# PCB-GONIO-V1_1.net
KiCad netlist of a schematic drawn in EAGLE
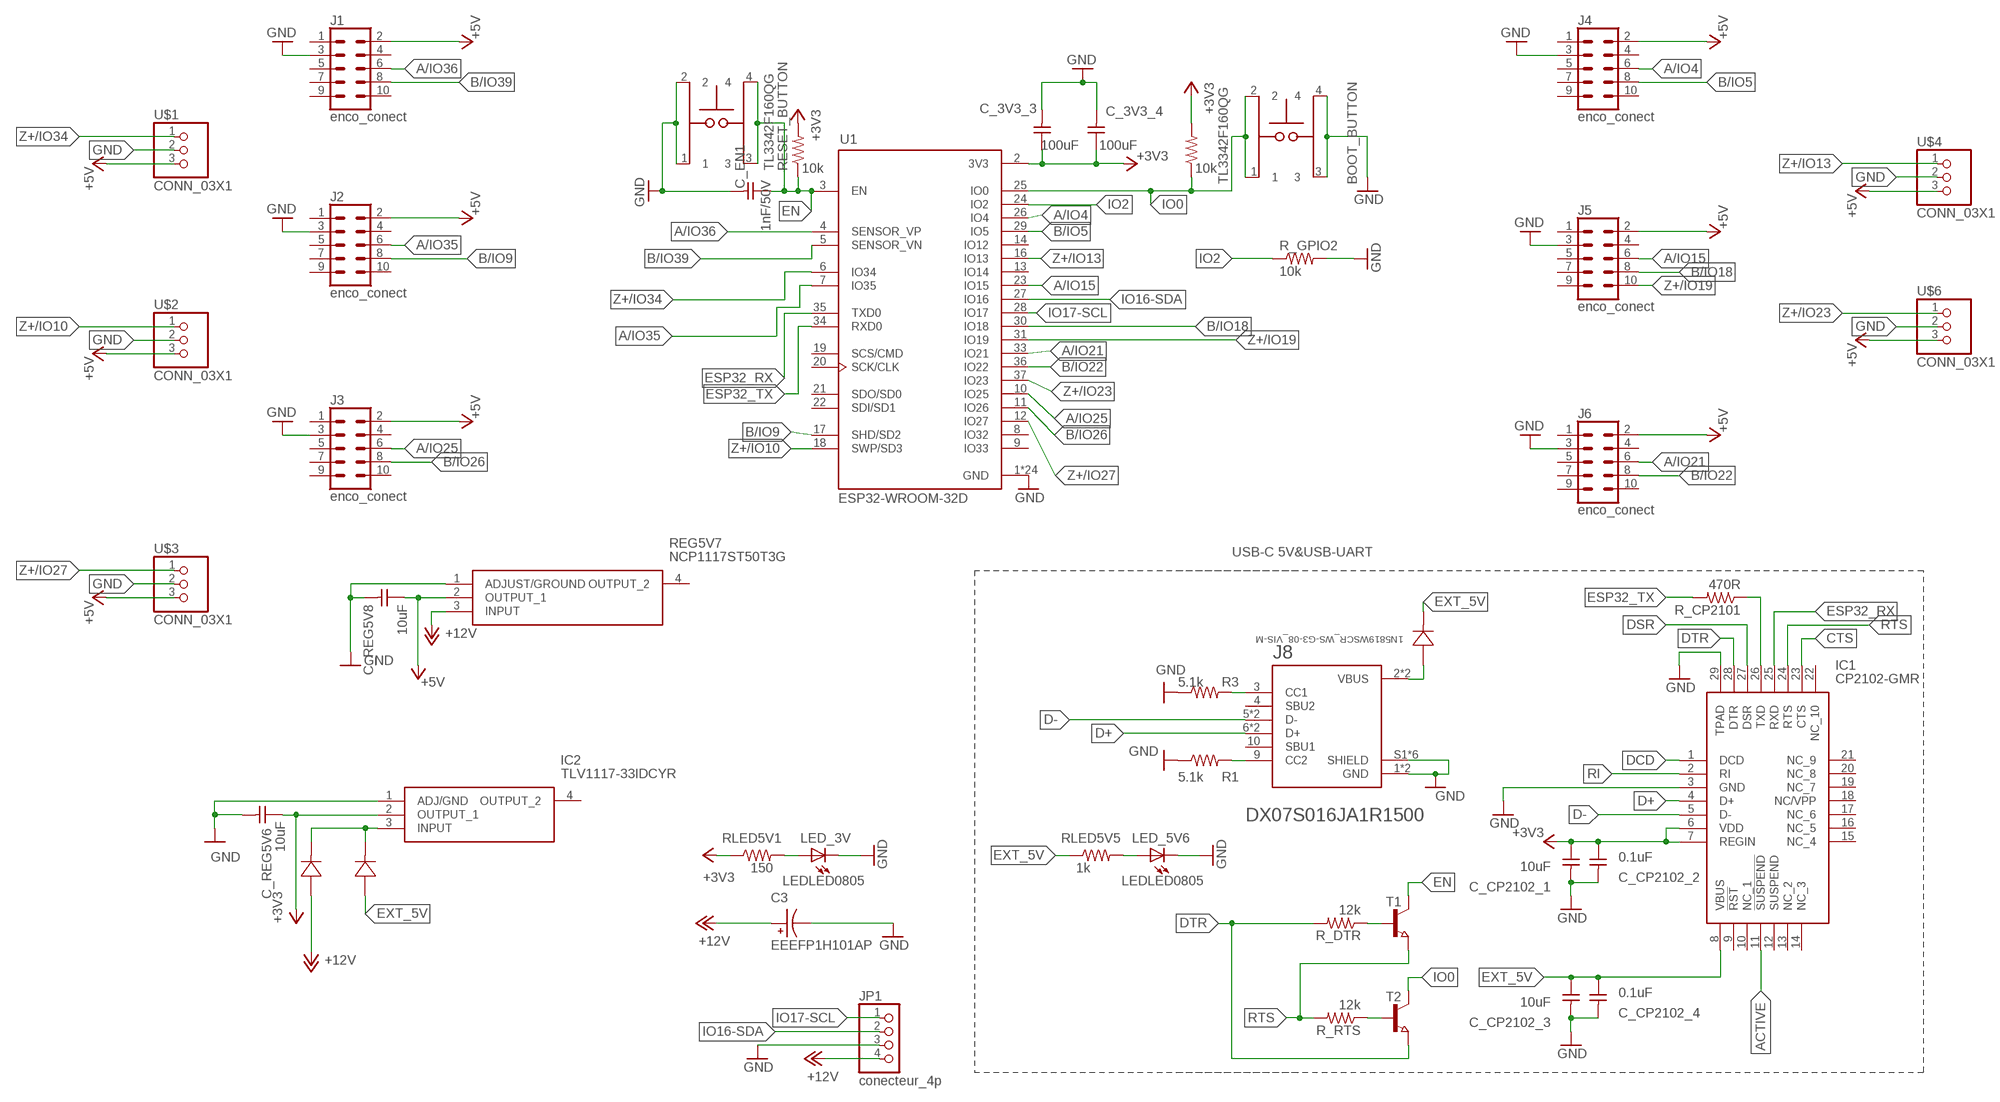
[diagram p0: schematic, sheet 1]

(export (version "E")
  (design (tool "Eeschema 10.0.6"))
  (components
    (comp (ref "BOOT_BUTTON")
      (value "TL3342F160QG")
      (footprint "eagle-import:SW_TL3342F160QG")
      (fields (field (name "MF") "E-Switch"))
      (libsource (lib "eagle-import") (part "TL3342F160QG"))
    )
    (comp (ref "C3")
      (value "EEEFP1H101AP")
      (footprint "eagle-import:CAP_EEEFP1H101AP")
      (fields (field (name "DIGIKEY_PART_NUMBER") "P19726TR-ND") (field (name "MF") "Panasonic"))
      (libsource (lib "eagle-import") (part "EEEFP1H101AP"))
    )
    (comp (ref "CR1")
      (value "1N5819WSCR_WS-G3-08_VIS-M")
      (footprint "eagle-import:CR_WS-G3-08_VIS-M")
      (fields
        (field (name "MANUFACTURER_PART_NUMBER") "1N4148WS-G3-08")
        (field (name "COPYRIGHT") "Copyright (C) 2022 Ultra Librarian. All rights reserved.")
      )
      (libsource (lib "eagle-import") (part "1N5819WSCR_WS-G3-08_VIS-M"))
    )
    (comp (ref "CR2")
      (value "1N5819WSCR_WS-G3-08_VIS-M")
      (footprint "eagle-import:CR_WS-G3-08_VIS-M")
      (fields
        (field (name "MANUFACTURER_PART_NUMBER") "1N4148WS-G3-08")
        (field (name "COPYRIGHT") "Copyright (C) 2022 Ultra Librarian. All rights reserved.")
      )
      (libsource (lib "eagle-import") (part "1N5819WSCR_WS-G3-08_VIS-M"))
    )
    (comp (ref "CR3")
      (value "1N5819WSCR_WS-G3-08_VIS-M")
      (footprint "eagle-import:CR_WS-G3-08_VIS-M")
      (fields
        (field (name "MANUFACTURER_PART_NUMBER") "1N4148WS-G3-08")
        (field (name "COPYRIGHT") "Copyright (C) 2022 Ultra Librarian. All rights reserved.")
      )
      (libsource (lib "eagle-import") (part "1N5819WSCR_WS-G3-08_VIS-M"))
    )
    (comp (ref "C_3V3_3")
      (value "100uF")
      (footprint "eagle-import:C1206FAB")
      (libsource (lib "eagle-import") (part "CAP_UNPOLARIZEDFAB"))
    )
    (comp (ref "C_3V3_4")
      (value "100uF")
      (footprint "eagle-import:C1206FAB")
      (libsource (lib "eagle-import") (part "CAP_UNPOLARIZEDFAB"))
    )
    (comp (ref "C_CP2102_1")
      (value "10uF")
      (footprint "eagle-import:C1206FAB")
      (libsource (lib "eagle-import") (part "CAP_UNPOLARIZEDFAB"))
    )
    (comp (ref "C_CP2102_2")
      (value "0.1uF")
      (footprint "eagle-import:C1206FAB")
      (libsource (lib "eagle-import") (part "CAP_UNPOLARIZEDFAB"))
    )
    (comp (ref "C_CP2102_3")
      (value "10uF")
      (footprint "eagle-import:C1206FAB")
      (libsource (lib "eagle-import") (part "CAP_UNPOLARIZEDFAB"))
    )
    (comp (ref "C_CP2102_4")
      (value "0.1uF")
      (footprint "eagle-import:C1206FAB")
      (libsource (lib "eagle-import") (part "CAP_UNPOLARIZEDFAB"))
    )
    (comp (ref "C_EN1")
      (value "1nF/50V")
      (footprint "eagle-import:C1206FAB")
      (libsource (lib "eagle-import") (part "CAP_UNPOLARIZEDFAB"))
    )
    (comp (ref "C_REG5V6")
      (value "10uF")
      (footprint "eagle-import:C1206FAB")
      (libsource (lib "eagle-import") (part "CAP_UNPOLARIZEDFAB"))
    )
    (comp (ref "C_REG5V8")
      (value "10uF")
      (footprint "eagle-import:C1206FAB")
      (libsource (lib "eagle-import") (part "CAP_UNPOLARIZEDFAB"))
    )
    (comp (ref "IC1")
      (value "CP2102-GMR")
      (footprint "eagle-import:QFN50P500X500X100-29N")
      (fields (field (name "MOUSER_PART_NUMBER") "634-CP2102-GMR"))
      (libsource (lib "eagle-import") (part "CP2102-GMR"))
    )
    (comp (ref "IC2")
      (value "TLV1117-33IDCYR")
      (footprint "eagle-import:SOT230P700X180-4N")
      (fields (field (name "MOUSER_PART_NUMBER") "595-TLV1117-33IDCYR"))
      (libsource (lib "eagle-import") (part "TLV1117-33IDCYR"))
    )
    (comp (ref "J1")
      (value "enco_conect")
      (footprint "eagle-import:2X5-SHROUDED")
      (libsource (lib "eagle-import") (part "CONN_05X2SHD"))
    )
    (comp (ref "J2")
      (value "enco_conect")
      (footprint "eagle-import:2X5-SHROUDED")
      (libsource (lib "eagle-import") (part "CONN_05X2SHD"))
    )
    (comp (ref "J3")
      (value "enco_conect")
      (footprint "eagle-import:2X5-SHROUDED")
      (libsource (lib "eagle-import") (part "CONN_05X2SHD"))
    )
    (comp (ref "J4")
      (value "enco_conect")
      (footprint "eagle-import:2X5-SHROUDED")
      (libsource (lib "eagle-import") (part "CONN_05X2SHD"))
    )
    (comp (ref "J5")
      (value "enco_conect")
      (footprint "eagle-import:2X5-SHROUDED")
      (libsource (lib "eagle-import") (part "CONN_05X2SHD"))
    )
    (comp (ref "J6")
      (value "enco_conect")
      (footprint "eagle-import:2X5-SHROUDED")
      (libsource (lib "eagle-import") (part "CONN_05X2SHD"))
    )
    (comp (ref "J8")
      (value "DX07S016JA1R1500")
      (footprint "eagle-import:JAE_DX07S016JA1R1500")
      (fields (field (name "MF") "Japan Aviation Electronics"))
      (libsource (lib "eagle-import") (part "DX07S016JA1R1500"))
    )
    (comp (ref "JP1")
      (value "conecteur_4p")
      (footprint "eagle-import:1X04")
      (libsource (lib "eagle-import") (part "PINHD-1X4"))
    )
    (comp (ref "LED_3V")
      (value "LEDLED0805")
      (footprint "eagle-import:LEDC2012X90N")
      (libsource (lib "eagle-import") (part "LEDLED0805"))
    )
    (comp (ref "LED_5V6")
      (value "LEDLED0805")
      (footprint "eagle-import:LEDC2012X90N")
      (libsource (lib "eagle-import") (part "LEDLED0805"))
    )
    (comp (ref "R1")
      (value "5.1k")
      (footprint "eagle-import:R1206W")
      (libsource (lib "eagle-import") (part "R-US_R1206W"))
    )
    (comp (ref "R3")
      (value "5.1k")
      (footprint "eagle-import:R1206W")
      (libsource (lib "eagle-import") (part "R-US_R1206W"))
    )
    (comp (ref "REG5V7")
      (value "NCP1117ST50T3G")
      (footprint "eagle-import:SOT230P700X180-4N")
      (fields (field (name "LCSC_PART") "C17314") (field (name "RS_PART_NUMBER") "8022130P"))
      (libsource (lib "eagle-import") (part "NCP1117ST50T3G"))
    )
    (comp (ref "RESET_BUTTON")
      (value "TL3342F160QG")
      (footprint "eagle-import:SW_TL3342F160QG")
      (fields (field (name "MF") "E-Switch"))
      (libsource (lib "eagle-import") (part "TL3342F160QG"))
    )
    (comp (ref "RLED5V1")
      (value "150")
      (footprint "eagle-import:R1206FAB")
      (libsource (lib "eagle-import") (part "R1206FAB"))
    )
    (comp (ref "RLED5V5")
      (value "1k")
      (footprint "eagle-import:R1206FAB")
      (libsource (lib "eagle-import") (part "R1206FAB"))
    )
    (comp (ref "R_CP2101")
      (value "470R")
      (footprint "eagle-import:R1206FAB")
      (libsource (lib "eagle-import") (part "R1206FAB"))
    )
    (comp (ref "R_DTR")
      (value "12k")
      (footprint "eagle-import:R1206FAB")
      (libsource (lib "eagle-import") (part "R1206FAB"))
    )
    (comp (ref "R_GPIO2")
      (value "10k")
      (footprint "eagle-import:R1206FAB")
      (libsource (lib "eagle-import") (part "R1206FAB"))
    )
    (comp (ref "R_PULL_UP1")
      (value "10k")
      (footprint "eagle-import:R1206FAB")
      (libsource (lib "eagle-import") (part "R1206FAB"))
    )
    (comp (ref "R_PULL_UP3")
      (value "10k")
      (footprint "eagle-import:R1206FAB")
      (libsource (lib "eagle-import") (part "R1206FAB"))
    )
    (comp (ref "R_RTS")
      (value "12k")
      (footprint "eagle-import:R1206FAB")
      (libsource (lib "eagle-import") (part "R1206FAB"))
    )
    (comp (ref "T1")
      (value "T_NPN_S8050-J3Y_CHANGJ_SOT23-BEC")
      (footprint "eagle-import:SOT23")
      (fields (field (name "LCSC_PART") "C2146"))
      (libsource (lib "eagle-import") (part "T_NPN__SOT23-BECS8050-J3Y_CHANGJ"))
    )
    (comp (ref "T2")
      (value "T_NPN_S8050-J3Y_CHANGJ_SOT23-BEC")
      (footprint "eagle-import:SOT23")
      (fields (field (name "LCSC_PART") "C2146"))
      (libsource (lib "eagle-import") (part "T_NPN__SOT23-BECS8050-J3Y_CHANGJ"))
    )
    (comp (ref "U$1")
      (value "CONN_03X1")
      (footprint "eagle-import:1X3")
      (libsource (lib "eagle-import") (part "CONN_03X1"))
    )
    (comp (ref "U$2")
      (value "CONN_03X1")
      (footprint "eagle-import:1X3")
      (libsource (lib "eagle-import") (part "CONN_03X1"))
    )
    (comp (ref "U$3")
      (value "CONN_03X1")
      (footprint "eagle-import:1X3")
      (libsource (lib "eagle-import") (part "CONN_03X1"))
    )
    (comp (ref "U$4")
      (value "CONN_03X1")
      (footprint "eagle-import:1X3")
      (libsource (lib "eagle-import") (part "CONN_03X1"))
    )
    (comp (ref "U$6")
      (value "CONN_03X1")
      (footprint "eagle-import:1X3")
      (libsource (lib "eagle-import") (part "CONN_03X1"))
    )
    (comp (ref "U1")
      (value "ESP32-WROOM-32D")
      (footprint "eagle-import:MODULE_ESP32-WROOM-32D")
      (fields (field (name "MF") "Espressif Systems"))
      (libsource (lib "eagle-import") (part "ESP32-WROOM-32D"))
    )
  )
  (nets
    (net (code "1") (name "+3V3") (class "Default")
      (node (ref "C_3V3_3") (pin "1") (pinfunction "1_1") (pintype "passive"))
      (node (ref "C_3V3_4") (pin "1") (pinfunction "1_1") (pintype "passive"))
      (node (ref "C_CP2102_1") (pin "1") (pinfunction "1_1") (pintype "passive"))
      (node (ref "C_CP2102_2") (pin "1") (pinfunction "1_1") (pintype "passive"))
      (node (ref "C_REG5V6") (pin "1") (pinfunction "1_1") (pintype "passive"))
      (node (ref "IC1") (pin "6") (pinfunction "VDD_6") (pintype "bidirectional"))
      (node (ref "IC1") (pin "7") (pinfunction "REGIN_7") (pintype "bidirectional"))
      (node (ref "IC2") (pin "2") (pinfunction "OUTPUT_1_2") (pintype "bidirectional"))
      (node (ref "RLED5V1") (pin "1") (pinfunction "1_1") (pintype "passive"))
      (node (ref "R_PULL_UP1") (pin "2") (pinfunction "2_2") (pintype "passive"))
      (node (ref "R_PULL_UP3") (pin "2") (pinfunction "2_2") (pintype "passive"))
      (node (ref "U1") (pin "2") (pinfunction "3V3_2") (pintype "power_in"))
    )
    (net (code "2") (name "+5V") (class "Default")
      (node (ref "C_REG5V8") (pin "1") (pinfunction "1_1") (pintype "passive"))
      (node (ref "J1") (pin "2") (pinfunction "2_2") (pintype "passive"))
      (node (ref "J2") (pin "2") (pinfunction "2_2") (pintype "passive"))
      (node (ref "J3") (pin "2") (pinfunction "2_2") (pintype "passive"))
      (node (ref "J4") (pin "2") (pinfunction "2_2") (pintype "passive"))
      (node (ref "J5") (pin "2") (pinfunction "2_2") (pintype "passive"))
      (node (ref "J6") (pin "2") (pinfunction "2_2") (pintype "passive"))
      (node (ref "REG5V7") (pin "2") (pinfunction "OUTPUT_1_2") (pintype "bidirectional"))
      (node (ref "U$1") (pin "3") (pinfunction "3_3") (pintype "passive"))
      (node (ref "U$2") (pin "3") (pinfunction "3_3") (pintype "passive"))
      (node (ref "U$3") (pin "3") (pinfunction "3_3") (pintype "passive"))
      (node (ref "U$4") (pin "3") (pinfunction "3_3") (pintype "passive"))
      (node (ref "U$6") (pin "3") (pinfunction "3_3") (pintype "passive"))
    )
    (net (code "3") (name "+12V") (class "Default")
      (node (ref "C3") (pin "1") (pinfunction "1_1") (pintype "passive"))
      (node (ref "CR2") (pin "2") (pinfunction "2_2") (pintype "passive"))
      (node (ref "JP1") (pin "4") (pinfunction "4_4") (pintype "passive"))
      (node (ref "REG5V7") (pin "3") (pinfunction "INPUT_3") (pintype "bidirectional"))
    )
    (net (code "4") (name "ACTIVE") (class "Default")
      (node (ref "IC1") (pin "11") (pinfunction "~{SUSPEND}_11") (pintype "bidirectional"))
    )
    (net (code "5") (name "A{slash}IO4") (class "Default")
      (node (ref "J4") (pin "6") (pinfunction "6_6") (pintype "passive"))
      (node (ref "U1") (pin "26") (pinfunction "IO4_26") (pintype "bidirectional"))
    )
    (net (code "6") (name "A{slash}IO15") (class "Default")
      (node (ref "J5") (pin "6") (pinfunction "6_6") (pintype "passive"))
      (node (ref "U1") (pin "23") (pinfunction "IO15_23") (pintype "bidirectional"))
    )
    (net (code "7") (name "A{slash}IO21") (class "Default")
      (node (ref "J6") (pin "6") (pinfunction "6_6") (pintype "passive"))
      (node (ref "U1") (pin "33") (pinfunction "IO21_33") (pintype "bidirectional"))
    )
    (net (code "8") (name "A{slash}IO25") (class "Default")
      (node (ref "J3") (pin "6") (pinfunction "6_6") (pintype "passive"))
      (node (ref "U1") (pin "10") (pinfunction "IO25_10") (pintype "bidirectional"))
    )
    (net (code "9") (name "A{slash}IO35") (class "Default")
      (node (ref "J2") (pin "6") (pinfunction "6_6") (pintype "passive"))
      (node (ref "U1") (pin "7") (pinfunction "IO35_7") (pintype "input"))
    )
    (net (code "10") (name "A{slash}IO36") (class "Default")
      (node (ref "J1") (pin "6") (pinfunction "6_6") (pintype "passive"))
      (node (ref "U1") (pin "4") (pinfunction "SENSOR_VP_4") (pintype "input"))
    )
    (net (code "11") (name "B{slash}IO5") (class "Default")
      (node (ref "J4") (pin "8") (pinfunction "8_8") (pintype "passive"))
      (node (ref "U1") (pin "29") (pinfunction "IO5_29") (pintype "bidirectional"))
    )
    (net (code "12") (name "B{slash}IO9") (class "Default")
      (node (ref "J2") (pin "8") (pinfunction "8_8") (pintype "passive"))
      (node (ref "U1") (pin "17") (pinfunction "SHD/SD2_17") (pintype "bidirectional"))
    )
    (net (code "13") (name "B{slash}IO18") (class "Default")
      (node (ref "J5") (pin "8") (pinfunction "8_8") (pintype "passive"))
      (node (ref "U1") (pin "30") (pinfunction "IO18_30") (pintype "bidirectional"))
    )
    (net (code "14") (name "B{slash}IO22") (class "Default")
      (node (ref "J6") (pin "8") (pinfunction "8_8") (pintype "passive"))
      (node (ref "U1") (pin "36") (pinfunction "IO22_36") (pintype "bidirectional"))
    )
    (net (code "15") (name "B{slash}IO26") (class "Default")
      (node (ref "J3") (pin "8") (pinfunction "8_8") (pintype "passive"))
      (node (ref "U1") (pin "11") (pinfunction "IO26_11") (pintype "bidirectional"))
    )
    (net (code "16") (name "B{slash}IO39") (class "Default")
      (node (ref "J1") (pin "8") (pinfunction "8_8") (pintype "passive"))
      (node (ref "U1") (pin "5") (pinfunction "SENSOR_VN_5") (pintype "input"))
    )
    (net (code "17") (name "CTS") (class "Default")
      (node (ref "IC1") (pin "23") (pinfunction "CTS_23") (pintype "bidirectional"))
    )
    (net (code "18") (name "D+") (class "Default")
      (node (ref "IC1") (pin "4") (pinfunction "D+_4") (pintype "bidirectional"))
      (node (ref "J8") (pin "6") (pinfunction "D+_6") (pintype "passive"))
      (node (ref "J8") (pin "7") (pinfunction "D+_7") (pintype "passive"))
    )
    (net (code "19") (name "D-") (class "Default")
      (node (ref "IC1") (pin "5") (pinfunction "D-_5") (pintype "bidirectional"))
      (node (ref "J8") (pin "5") (pinfunction "D-_5") (pintype "passive"))
      (node (ref "J8") (pin "8") (pinfunction "D-_8") (pintype "passive"))
    )
    (net (code "20") (name "DCD") (class "Default")
      (node (ref "IC1") (pin "1") (pinfunction "DCD_1") (pintype "bidirectional"))
    )
    (net (code "21") (name "DSR") (class "Default")
      (node (ref "IC1") (pin "27") (pinfunction "DSR_27") (pintype "bidirectional"))
    )
    (net (code "22") (name "DTR") (class "Default")
      (node (ref "IC1") (pin "28") (pinfunction "DTR_28") (pintype "bidirectional"))
      (node (ref "R_DTR") (pin "2") (pinfunction "2_2") (pintype "passive"))
      (node (ref "T2") (pin "2") (pinfunction "E_2") (pintype "passive"))
    )
    (net (code "23") (name "EN") (class "Default")
      (node (ref "C_EN1") (pin "1") (pinfunction "1_1") (pintype "passive"))
      (node (ref "RESET_BUTTON") (pin "3") (pinfunction "3_3") (pintype "passive"))
      (node (ref "RESET_BUTTON") (pin "4") (pinfunction "4_4") (pintype "passive"))
      (node (ref "R_PULL_UP1") (pin "1") (pinfunction "1_1") (pintype "passive"))
      (node (ref "T1") (pin "3") (pinfunction "C_3") (pintype "passive"))
      (node (ref "U1") (pin "3") (pinfunction "EN_3") (pintype "input"))
    )
    (net (code "24") (name "ESP32_RX") (class "Default")
      (node (ref "IC1") (pin "25") (pinfunction "RXD_25") (pintype "bidirectional"))
      (node (ref "U1") (pin "35") (pinfunction "TXD0_35") (pintype "bidirectional"))
    )
    (net (code "25") (name "ESP32_TX") (class "Default")
      (node (ref "R_CP2101") (pin "2") (pinfunction "2_2") (pintype "passive"))
      (node (ref "U1") (pin "34") (pinfunction "RXD0_34") (pintype "bidirectional"))
    )
    (net (code "26") (name "EXT_5V") (class "Default")
      (node (ref "CR1") (pin "1") (pinfunction "1_1") (pintype "passive"))
      (node (ref "CR3") (pin "2") (pinfunction "2_2") (pintype "passive"))
      (node (ref "C_CP2102_3") (pin "1") (pinfunction "1_1") (pintype "passive"))
      (node (ref "C_CP2102_4") (pin "1") (pinfunction "1_1") (pintype "passive"))
      (node (ref "IC1") (pin "8") (pinfunction "VBUS_8") (pintype "bidirectional"))
      (node (ref "RLED5V5") (pin "1") (pinfunction "1_1") (pintype "passive"))
    )
    (net (code "27") (name "GND") (class "Default")
      (node (ref "BOOT_BUTTON") (pin "3") (pinfunction "3_3") (pintype "passive"))
      (node (ref "BOOT_BUTTON") (pin "4") (pinfunction "4_4") (pintype "passive"))
      (node (ref "C3") (pin "2") (pinfunction "2_2") (pintype "passive"))
      (node (ref "C_3V3_3") (pin "2") (pinfunction "2_2") (pintype "passive"))
      (node (ref "C_3V3_4") (pin "2") (pinfunction "2_2") (pintype "passive"))
      (node (ref "C_CP2102_1") (pin "2") (pinfunction "2_2") (pintype "passive"))
      (node (ref "C_CP2102_2") (pin "2") (pinfunction "2_2") (pintype "passive"))
      (node (ref "C_CP2102_3") (pin "2") (pinfunction "2_2") (pintype "passive"))
      (node (ref "C_CP2102_4") (pin "2") (pinfunction "2_2") (pintype "passive"))
      (node (ref "C_EN1") (pin "2") (pinfunction "2_2") (pintype "passive"))
      (node (ref "C_REG5V6") (pin "2") (pinfunction "2_2") (pintype "passive"))
      (node (ref "C_REG5V8") (pin "2") (pinfunction "2_2") (pintype "passive"))
      (node (ref "IC1") (pin "29") (pinfunction "TPAD_29") (pintype "bidirectional"))
      (node (ref "IC1") (pin "3") (pinfunction "GND_3") (pintype "bidirectional"))
      (node (ref "IC2") (pin "1") (pinfunction "ADJ/GND_1") (pintype "bidirectional"))
      (node (ref "J1") (pin "3") (pinfunction "3_3") (pintype "passive"))
      (node (ref "J2") (pin "3") (pinfunction "3_3") (pintype "passive"))
      (node (ref "J3") (pin "3") (pinfunction "3_3") (pintype "passive"))
      (node (ref "J4") (pin "3") (pinfunction "3_3") (pintype "passive"))
      (node (ref "J5") (pin "3") (pinfunction "3_3") (pintype "passive"))
      (node (ref "J6") (pin "3") (pinfunction "3_3") (pintype "passive"))
      (node (ref "J8") (pin "1") (pinfunction "GND_1") (pintype "power_in"))
      (node (ref "J8") (pin "12") (pinfunction "GND_12") (pintype "power_in"))
      (node (ref "J8") (pin "S1") (pinfunction "SHIELD_S1") (pintype "passive"))
      (node (ref "J8") (pin "S2") (pinfunction "SHIELD_S2") (pintype "passive"))
      (node (ref "J8") (pin "S3") (pinfunction "SHIELD_S3") (pintype "passive"))
      (node (ref "J8") (pin "S4") (pinfunction "SHIELD_S4") (pintype "passive"))
      (node (ref "J8") (pin "S5") (pinfunction "SHIELD_S5") (pintype "passive"))
      (node (ref "J8") (pin "S6") (pinfunction "SHIELD_S6") (pintype "passive"))
      (node (ref "JP1") (pin "3") (pinfunction "3_3") (pintype "passive"))
      (node (ref "LED_3V") (pin "1") (pinfunction "C_1") (pintype "passive"))
      (node (ref "LED_5V6") (pin "1") (pinfunction "C_1") (pintype "passive"))
      (node (ref "R1") (pin "1") (pinfunction "1_1") (pintype "passive"))
      (node (ref "R3") (pin "1") (pinfunction "1_1") (pintype "passive"))
      (node (ref "REG5V7") (pin "1") (pinfunction "ADJUST/GROUND_1") (pintype "bidirectional"))
      (node (ref "RESET_BUTTON") (pin "1") (pinfunction "1_1") (pintype "passive"))
      (node (ref "RESET_BUTTON") (pin "2") (pinfunction "2_2") (pintype "passive"))
      (node (ref "R_GPIO2") (pin "2") (pinfunction "2_2") (pintype "passive"))
      (node (ref "U$1") (pin "2") (pinfunction "2_2") (pintype "passive"))
      (node (ref "U$2") (pin "2") (pinfunction "2_2") (pintype "passive"))
      (node (ref "U$3") (pin "2") (pinfunction "2_2") (pintype "passive"))
      (node (ref "U$4") (pin "2") (pinfunction "2_2") (pintype "passive"))
      (node (ref "U$6") (pin "2") (pinfunction "2_2") (pintype "passive"))
      (node (ref "U1") (pin "1") (pinfunction "GND_1") (pintype "power_in"))
      (node (ref "U1") (pin "15") (pinfunction "GND_15") (pintype "power_in"))
      (node (ref "U1") (pin "38") (pinfunction "GND_38") (pintype "power_in"))
      (node (ref "U1") (pin "39_1") (pinfunction "GND_39_1") (pintype "power_in"))
      (node (ref "U1") (pin "39_10") (pinfunction "GND_39_10") (pintype "power_in"))
      (node (ref "U1") (pin "39_11") (pinfunction "GND_39_11") (pintype "power_in"))
      (node (ref "U1") (pin "39_12") (pinfunction "GND_39_12") (pintype "power_in"))
      (node (ref "U1") (pin "39_13") (pinfunction "GND_39_13") (pintype "power_in"))
      (node (ref "U1") (pin "39_14") (pinfunction "GND_39_14") (pintype "power_in"))
      (node (ref "U1") (pin "39_15") (pinfunction "GND_39_15") (pintype "power_in"))
      (node (ref "U1") (pin "39_16") (pinfunction "GND_39_16") (pintype "power_in"))
      (node (ref "U1") (pin "39_17") (pinfunction "GND_39_17") (pintype "power_in"))
      (node (ref "U1") (pin "39_18") (pinfunction "GND_39_18") (pintype "power_in"))
      (node (ref "U1") (pin "39_19") (pinfunction "GND_39_19") (pintype "power_in"))
      (node (ref "U1") (pin "39_2") (pinfunction "GND_39_2") (pintype "power_in"))
      (node (ref "U1") (pin "39_20") (pinfunction "GND_39_20") (pintype "power_in"))
      (node (ref "U1") (pin "39_21") (pinfunction "GND_39_21") (pintype "power_in"))
      (node (ref "U1") (pin "39_3") (pinfunction "GND_39_3") (pintype "power_in"))
      (node (ref "U1") (pin "39_4") (pinfunction "GND_39_4") (pintype "power_in"))
      (node (ref "U1") (pin "39_5") (pinfunction "GND_39_5") (pintype "power_in"))
      (node (ref "U1") (pin "39_6") (pinfunction "GND_39_6") (pintype "power_in"))
      (node (ref "U1") (pin "39_7") (pinfunction "GND_39_7") (pintype "power_in"))
      (node (ref "U1") (pin "39_8") (pinfunction "GND_39_8") (pintype "power_in"))
      (node (ref "U1") (pin "39_9") (pinfunction "GND_39_9") (pintype "power_in"))
    )
    (net (code "28") (name "IO0") (class "Default")
      (node (ref "BOOT_BUTTON") (pin "1") (pinfunction "1_1") (pintype "passive"))
      (node (ref "BOOT_BUTTON") (pin "2") (pinfunction "2_2") (pintype "passive"))
      (node (ref "R_PULL_UP3") (pin "1") (pinfunction "1_1") (pintype "passive"))
      (node (ref "T2") (pin "3") (pinfunction "C_3") (pintype "passive"))
      (node (ref "U1") (pin "25") (pinfunction "IO0_25") (pintype "bidirectional"))
    )
    (net (code "29") (name "IO2") (class "Default")
      (node (ref "R_GPIO2") (pin "1") (pinfunction "1_1") (pintype "passive"))
      (node (ref "U1") (pin "24") (pinfunction "IO2_24") (pintype "bidirectional"))
    )
    (net (code "30") (name "IO16-SDA") (class "Default")
      (node (ref "JP1") (pin "2") (pinfunction "2_2") (pintype "passive"))
      (node (ref "U1") (pin "27") (pinfunction "IO16_27") (pintype "bidirectional"))
    )
    (net (code "31") (name "IO17-SCL") (class "Default")
      (node (ref "JP1") (pin "1") (pinfunction "1_1") (pintype "passive"))
      (node (ref "U1") (pin "28") (pinfunction "IO17_28") (pintype "bidirectional"))
    )
    (net (code "32") (name "Net-(CR1-Pad2)") (class "Default")
      (node (ref "CR1") (pin "2") (pinfunction "2_2") (pintype "passive"))
      (node (ref "J8") (pin "11") (pinfunction "VBUS_11") (pintype "power_in"))
      (node (ref "J8") (pin "2") (pinfunction "VBUS_2") (pintype "power_in"))
    )
    (net (code "33") (name "Net-(IC1-TXD)") (class "Default")
      (node (ref "IC1") (pin "26") (pinfunction "TXD_26") (pintype "bidirectional"))
      (node (ref "R_CP2101") (pin "1") (pinfunction "1_1") (pintype "passive"))
    )
    (net (code "34") (name "Net-(IC2-INPUT)") (class "Default")
      (node (ref "CR2") (pin "1") (pinfunction "1_1") (pintype "passive"))
      (node (ref "CR3") (pin "1") (pinfunction "1_1") (pintype "passive"))
      (node (ref "IC2") (pin "3") (pinfunction "INPUT_3") (pintype "bidirectional"))
    )
    (net (code "35") (name "Net-(J8-CC1)") (class "Default")
      (node (ref "J8") (pin "3") (pinfunction "CC1_3") (pintype "passive"))
      (node (ref "R3") (pin "2") (pinfunction "2_2") (pintype "passive"))
    )
    (net (code "36") (name "Net-(J8-CC2)") (class "Default")
      (node (ref "J8") (pin "9") (pinfunction "CC2_9") (pintype "passive"))
      (node (ref "R1") (pin "2") (pinfunction "2_2") (pintype "passive"))
    )
    (net (code "37") (name "Net-(LED_3V-A)") (class "Default")
      (node (ref "LED_3V") (pin "2") (pinfunction "A_2") (pintype "passive"))
      (node (ref "RLED5V1") (pin "2") (pinfunction "2_2") (pintype "passive"))
    )
    (net (code "38") (name "Net-(LED_5V6-A)") (class "Default")
      (node (ref "LED_5V6") (pin "2") (pinfunction "A_2") (pintype "passive"))
      (node (ref "RLED5V5") (pin "2") (pinfunction "2_2") (pintype "passive"))
    )
    (net (code "39") (name "Net-(T1-B)") (class "Default")
      (node (ref "R_DTR") (pin "1") (pinfunction "1_1") (pintype "passive"))
      (node (ref "T1") (pin "1") (pinfunction "B_1") (pintype "passive"))
    )
    (net (code "40") (name "Net-(T2-B)") (class "Default")
      (node (ref "R_RTS") (pin "1") (pinfunction "1_1") (pintype "passive"))
      (node (ref "T2") (pin "1") (pinfunction "B_1") (pintype "passive"))
    )
    (net (code "41") (name "RI") (class "Default")
      (node (ref "IC1") (pin "2") (pinfunction "RI_2") (pintype "bidirectional"))
    )
    (net (code "42") (name "RTS") (class "Default")
      (node (ref "IC1") (pin "24") (pinfunction "RTS_24") (pintype "bidirectional"))
      (node (ref "R_RTS") (pin "2") (pinfunction "2_2") (pintype "passive"))
      (node (ref "T1") (pin "2") (pinfunction "E_2") (pintype "passive"))
    )
    (net (code "43") (name "Z+{slash}IO10") (class "Default")
      (node (ref "U$2") (pin "1") (pinfunction "1_1") (pintype "passive"))
      (node (ref "U1") (pin "18") (pinfunction "SWP/SD3_18") (pintype "bidirectional"))
    )
    (net (code "44") (name "Z+{slash}IO13") (class "Default")
      (node (ref "U$4") (pin "1") (pinfunction "1_1") (pintype "passive"))
      (node (ref "U1") (pin "16") (pinfunction "IO13_16") (pintype "bidirectional"))
    )
    (net (code "45") (name "Z+{slash}IO19") (class "Default")
      (node (ref "J5") (pin "10") (pinfunction "10_10") (pintype "passive"))
      (node (ref "U1") (pin "31") (pinfunction "IO19_31") (pintype "bidirectional"))
    )
    (net (code "46") (name "Z+{slash}IO23") (class "Default")
      (node (ref "U$6") (pin "1") (pinfunction "1_1") (pintype "passive"))
      (node (ref "U1") (pin "37") (pinfunction "IO23_37") (pintype "bidirectional"))
    )
    (net (code "47") (name "Z+{slash}IO27") (class "Default")
      (node (ref "U$3") (pin "1") (pinfunction "1_1") (pintype "passive"))
      (node (ref "U1") (pin "12") (pinfunction "IO27_12") (pintype "bidirectional"))
    )
    (net (code "48") (name "Z+{slash}IO34") (class "Default")
      (node (ref "U$1") (pin "1") (pinfunction "1_1") (pintype "passive"))
      (node (ref "U1") (pin "6") (pinfunction "IO34_6") (pintype "input"))
    )
    (net (code "49") (name "unconnected-(IC1-NC_1-Pad10)") (class "Default")
      (node (ref "IC1") (pin "10") (pinfunction "NC_1_10") (pintype "bidirectional"))
    )
    (net (code "50") (name "unconnected-(IC1-NC_2-Pad13)") (class "Default")
      (node (ref "IC1") (pin "13") (pinfunction "NC_2_13") (pintype "bidirectional"))
    )
    (net (code "51") (name "unconnected-(IC1-NC_3-Pad14)") (class "Default")
      (node (ref "IC1") (pin "14") (pinfunction "NC_3_14") (pintype "bidirectional"))
    )
    (net (code "52") (name "unconnected-(IC1-NC_4-Pad15)") (class "Default")
      (node (ref "IC1") (pin "15") (pinfunction "NC_4_15") (pintype "bidirectional"))
    )
    (net (code "53") (name "unconnected-(IC1-NC_5-Pad16)") (class "Default")
      (node (ref "IC1") (pin "16") (pinfunction "NC_5_16") (pintype "bidirectional"))
    )
    (net (code "54") (name "unconnected-(IC1-NC_6-Pad17)") (class "Default")
      (node (ref "IC1") (pin "17") (pinfunction "NC_6_17") (pintype "bidirectional"))
    )
    (net (code "55") (name "unconnected-(IC1-NC_7-Pad19)") (class "Default")
      (node (ref "IC1") (pin "19") (pinfunction "NC_7_19") (pintype "bidirectional"))
    )
    (net (code "56") (name "unconnected-(IC1-NC_8-Pad20)") (class "Default")
      (node (ref "IC1") (pin "20") (pinfunction "NC_8_20") (pintype "bidirectional"))
    )
    (net (code "57") (name "unconnected-(IC1-NC_9-Pad21)") (class "Default")
      (node (ref "IC1") (pin "21") (pinfunction "NC_9_21") (pintype "bidirectional"))
    )
    (net (code "58") (name "unconnected-(IC1-NC_10-Pad22)") (class "Default")
      (node (ref "IC1") (pin "22") (pinfunction "NC_10_22") (pintype "bidirectional"))
    )
    (net (code "59") (name "unconnected-(IC1-NC{slash}VPP-Pad18)") (class "Default")
      (node (ref "IC1") (pin "18") (pinfunction "NC/VPP_18") (pintype "bidirectional"))
    )
    (net (code "60") (name "unconnected-(IC1-SUSPEND-Pad12)") (class "Default")
      (node (ref "IC1") (pin "12") (pinfunction "SUSPEND_12") (pintype "bidirectional"))
    )
    (net (code "61") (name "unconnected-(IC1-~{RST}-Pad9)") (class "Default")
      (node (ref "IC1") (pin "9") (pinfunction "~{RST}_9") (pintype "bidirectional"))
    )
    (net (code "62") (name "unconnected-(IC2-OUTPUT_2-Pad4)") (class "Default")
      (node (ref "IC2") (pin "4") (pinfunction "OUTPUT_2_4") (pintype "bidirectional"))
    )
    (net (code "63") (name "unconnected-(J1-Pad1)") (class "Default")
      (node (ref "J1") (pin "1") (pinfunction "1_1") (pintype "passive"))
    )
    (net (code "64") (name "unconnected-(J1-Pad4)") (class "Default")
      (node (ref "J1") (pin "4") (pinfunction "4_4") (pintype "passive"))
    )
    (net (code "65") (name "unconnected-(J1-Pad5)") (class "Default")
      (node (ref "J1") (pin "5") (pinfunction "5_5") (pintype "passive"))
    )
    (net (code "66") (name "unconnected-(J1-Pad7)") (class "Default")
      (node (ref "J1") (pin "7") (pinfunction "7_7") (pintype "passive"))
    )
    (net (code "67") (name "unconnected-(J1-Pad9)") (class "Default")
      (node (ref "J1") (pin "9") (pinfunction "9_9") (pintype "passive"))
    )
    (net (code "68") (name "unconnected-(J1-Pad10)") (class "Default")
      (node (ref "J1") (pin "10") (pinfunction "10_10") (pintype "passive"))
    )
    (net (code "69") (name "unconnected-(J2-Pad1)") (class "Default")
      (node (ref "J2") (pin "1") (pinfunction "1_1") (pintype "passive"))
    )
    (net (code "70") (name "unconnected-(J2-Pad4)") (class "Default")
      (node (ref "J2") (pin "4") (pinfunction "4_4") (pintype "passive"))
    )
    (net (code "71") (name "unconnected-(J2-Pad5)") (class "Default")
      (node (ref "J2") (pin "5") (pinfunction "5_5") (pintype "passive"))
    )
    (net (code "72") (name "unconnected-(J2-Pad7)") (class "Default")
      (node (ref "J2") (pin "7") (pinfunction "7_7") (pintype "passive"))
    )
    (net (code "73") (name "unconnected-(J2-Pad9)") (class "Default")
      (node (ref "J2") (pin "9") (pinfunction "9_9") (pintype "passive"))
    )
    (net (code "74") (name "unconnected-(J2-Pad10)") (class "Default")
      (node (ref "J2") (pin "10") (pinfunction "10_10") (pintype "passive"))
    )
    (net (code "75") (name "unconnected-(J3-Pad1)") (class "Default")
      (node (ref "J3") (pin "1") (pinfunction "1_1") (pintype "passive"))
    )
    (net (code "76") (name "unconnected-(J3-Pad4)") (class "Default")
      (node (ref "J3") (pin "4") (pinfunction "4_4") (pintype "passive"))
    )
    (net (code "77") (name "unconnected-(J3-Pad5)") (class "Default")
      (node (ref "J3") (pin "5") (pinfunction "5_5") (pintype "passive"))
    )
    (net (code "78") (name "unconnected-(J3-Pad7)") (class "Default")
      (node (ref "J3") (pin "7") (pinfunction "7_7") (pintype "passive"))
    )
    (net (code "79") (name "unconnected-(J3-Pad9)") (class "Default")
      (node (ref "J3") (pin "9") (pinfunction "9_9") (pintype "passive"))
    )
    (net (code "80") (name "unconnected-(J3-Pad10)") (class "Default")
      (node (ref "J3") (pin "10") (pinfunction "10_10") (pintype "passive"))
    )
    (net (code "81") (name "unconnected-(J4-Pad1)") (class "Default")
      (node (ref "J4") (pin "1") (pinfunction "1_1") (pintype "passive"))
    )
    (net (code "82") (name "unconnected-(J4-Pad4)") (class "Default")
      (node (ref "J4") (pin "4") (pinfunction "4_4") (pintype "passive"))
    )
    (net (code "83") (name "unconnected-(J4-Pad5)") (class "Default")
      (node (ref "J4") (pin "5") (pinfunction "5_5") (pintype "passive"))
    )
    (net (code "84") (name "unconnected-(J4-Pad7)") (class "Default")
      (node (ref "J4") (pin "7") (pinfunction "7_7") (pintype "passive"))
    )
    (net (code "85") (name "unconnected-(J4-Pad9)") (class "Default")
      (node (ref "J4") (pin "9") (pinfunction "9_9") (pintype "passive"))
    )
    (net (code "86") (name "unconnected-(J4-Pad10)") (class "Default")
      (node (ref "J4") (pin "10") (pinfunction "10_10") (pintype "passive"))
    )
    (net (code "87") (name "unconnected-(J5-Pad1)") (class "Default")
      (node (ref "J5") (pin "1") (pinfunction "1_1") (pintype "passive"))
    )
    (net (code "88") (name "unconnected-(J5-Pad4)") (class "Default")
      (node (ref "J5") (pin "4") (pinfunction "4_4") (pintype "passive"))
    )
    (net (code "89") (name "unconnected-(J5-Pad5)") (class "Default")
      (node (ref "J5") (pin "5") (pinfunction "5_5") (pintype "passive"))
    )
    (net (code "90") (name "unconnected-(J5-Pad7)") (class "Default")
      (node (ref "J5") (pin "7") (pinfunction "7_7") (pintype "passive"))
    )
    (net (code "91") (name "unconnected-(J5-Pad9)") (class "Default")
      (node (ref "J5") (pin "9") (pinfunction "9_9") (pintype "passive"))
    )
    (net (code "92") (name "unconnected-(J6-Pad1)") (class "Default")
      (node (ref "J6") (pin "1") (pinfunction "1_1") (pintype "passive"))
    )
    (net (code "93") (name "unconnected-(J6-Pad4)") (class "Default")
      (node (ref "J6") (pin "4") (pinfunction "4_4") (pintype "passive"))
    )
    (net (code "94") (name "unconnected-(J6-Pad5)") (class "Default")
      (node (ref "J6") (pin "5") (pinfunction "5_5") (pintype "passive"))
    )
    (net (code "95") (name "unconnected-(J6-Pad7)") (class "Default")
      (node (ref "J6") (pin "7") (pinfunction "7_7") (pintype "passive"))
    )
    (net (code "96") (name "unconnected-(J6-Pad9)") (class "Default")
      (node (ref "J6") (pin "9") (pinfunction "9_9") (pintype "passive"))
    )
    (net (code "97") (name "unconnected-(J6-Pad10)") (class "Default")
      (node (ref "J6") (pin "10") (pinfunction "10_10") (pintype "passive"))
    )
    (net (code "98") (name "unconnected-(J8-SBU1-Pad10)") (class "Default")
      (node (ref "J8") (pin "10") (pinfunction "SBU1_10") (pintype "passive"))
    )
    (net (code "99") (name "unconnected-(J8-SBU2-Pad4)") (class "Default")
      (node (ref "J8") (pin "4") (pinfunction "SBU2_4") (pintype "passive"))
    )
    (net (code "100") (name "unconnected-(REG5V7-OUTPUT_2-Pad4)") (class "Default")
      (node (ref "REG5V7") (pin "4") (pinfunction "OUTPUT_2_4") (pintype "bidirectional"))
    )
    (net (code "101") (name "unconnected-(U1-IO12-Pad14)") (class "Default")
      (node (ref "U1") (pin "14") (pinfunction "IO12_14") (pintype "bidirectional"))
    )
    (net (code "102") (name "unconnected-(U1-IO14-Pad13)") (class "Default")
      (node (ref "U1") (pin "13") (pinfunction "IO14_13") (pintype "bidirectional"))
    )
    (net (code "103") (name "unconnected-(U1-IO32-Pad8)") (class "Default")
      (node (ref "U1") (pin "8") (pinfunction "IO32_8") (pintype "bidirectional"))
    )
    (net (code "104") (name "unconnected-(U1-IO33-Pad9)") (class "Default")
      (node (ref "U1") (pin "9") (pinfunction "IO33_9") (pintype "bidirectional"))
    )
    (net (code "105") (name "unconnected-(U1-SCK{slash}CLK-Pad20)") (class "Default")
      (node (ref "U1") (pin "20") (pinfunction "SCK/CLK_20") (pintype "bidirectional"))
    )
    (net (code "106") (name "unconnected-(U1-SCS{slash}CMD-Pad19)") (class "Default")
      (node (ref "U1") (pin "19") (pinfunction "SCS/CMD_19") (pintype "bidirectional"))
    )
    (net (code "107") (name "unconnected-(U1-SDI{slash}SD1-Pad22)") (class "Default")
      (node (ref "U1") (pin "22") (pinfunction "SDI/SD1_22") (pintype "bidirectional"))
    )
    (net (code "108") (name "unconnected-(U1-SDO{slash}SD0-Pad21)") (class "Default")
      (node (ref "U1") (pin "21") (pinfunction "SDO/SD0_21") (pintype "bidirectional"))
    )
  )
)
